# attiny_x313_blink.net
KiCad netlist of a schematic drawn in EAGLE
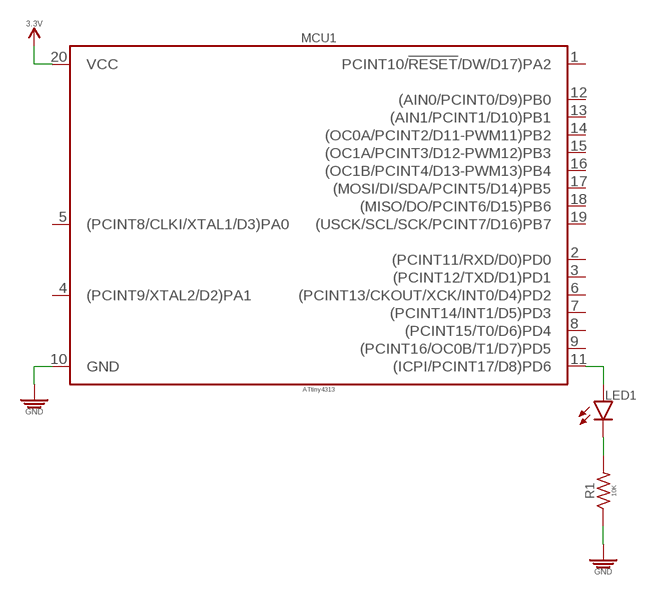
[diagram p0: schematic, sheet 1]

(export (version "E")
  (design (tool "Eeschema 10.0.6"))
  (components
    (comp (ref "LED1")
      (value "LED_PTH_T-1_3/4_5MM_NO-COLOR")
      (footprint "eagle-import:LED_PTH_T-1_3_4_5MM")
      (libsource (lib "eagle-import") (part "LED_PTH_T-1_3/4_5MM_NO-COLOR"))
    )
    (comp (ref "MCU1")
      (value "ATtiny4313")
      (footprint "eagle-import:DIP793W45P254L2573H533Q20B_DIP-20_ATTINY-X313")
      (fields (field (name "MFR") "Microchip Technology") (field (name "MPN") "ATTINY4313-PU"))
      (libsource (lib "eagle-import") (part "ATTINY-X313_DIP-20_ATTINY-4313"))
    )
    (comp (ref "R1")
      (value "10K")
      (footprint "eagle-import:RESAD660W45L340D190B")
      (fields (field (name "MFR") "Yageo") (field (name "MPN") "CFR-12JB-52-10K"))
      (libsource (lib "eagle-import") (part "10KΩ_PTH-204/7_1/6W-5%"))
    )
  )
  (nets
    (net (code "1") (name "3.3V") (class "Default")
      (node (ref "MCU1") (pin "20") (pinfunction "VCC_20") (pintype "passive"))
    )
    (net (code "2") (name "GND") (class "Default")
      (node (ref "MCU1") (pin "10") (pinfunction "GND_10") (pintype "passive"))
      (node (ref "R1") (pin "1") (pinfunction "1_1") (pintype "passive"))
    )
    (net (code "3") (name "Net-(LED1-PadK)") (class "Default")
      (node (ref "LED1") (pin "K") (pinfunction "K_K") (pintype "passive"))
      (node (ref "R1") (pin "2") (pinfunction "2_2") (pintype "passive"))
    )
    (net (code "4") (name "Net-(MCU1-(ICPI{slash}PCINT17{slash}D8)PD6)") (class "Default")
      (node (ref "LED1") (pin "A") (pinfunction "A_A") (pintype "passive"))
      (node (ref "MCU1") (pin "11") (pinfunction "(ICPI/PCINT17/D8)PD6_11") (pintype "bidirectional"))
    )
    (net (code "5") (name "unconnected-(MCU1-(AIN0{slash}PCINT0{slash}D9)PB0-Pad12)") (class "Default")
      (node (ref "MCU1") (pin "12") (pinfunction "(AIN0/PCINT0/D9)PB0_12") (pintype "bidirectional"))
    )
    (net (code "6") (name "unconnected-(MCU1-(AIN1{slash}PCINT1{slash}D10)PB1-Pad13)") (class "Default")
      (node (ref "MCU1") (pin "13") (pinfunction "(AIN1/PCINT1/D10)PB1_13") (pintype "bidirectional"))
    )
    (net (code "7") (name "unconnected-(MCU1-(MISO{slash}DO{slash}PCINT6{slash}D15)PB6-Pad18)") (class "Default")
      (node (ref "MCU1") (pin "18") (pinfunction "(MISO/DO/PCINT6/D15)PB6_18") (pintype "bidirectional"))
    )
    (net (code "8") (name "unconnected-(MCU1-(MOSI{slash}DI{slash}SDA{slash}PCINT5{slash}D14)PB5-Pad17)") (class "Default")
      (node (ref "MCU1") (pin "17") (pinfunction "(MOSI/DI/SDA/PCINT5/D14)PB5_17") (pintype "bidirectional"))
    )
    (net (code "9") (name "unconnected-(MCU1-(OC0A{slash}PCINT2{slash}D11-PWM11)PB2-Pad14)") (class "Default")
      (node (ref "MCU1") (pin "14") (pinfunction "(OC0A/PCINT2/D11-PWM11)PB2_14") (pintype "bidirectional"))
    )
    (net (code "10") (name "unconnected-(MCU1-(OC1A{slash}PCINT3{slash}D12-PWM12)PB3-Pad15)") (class "Default")
      (node (ref "MCU1") (pin "15") (pinfunction "(OC1A/PCINT3/D12-PWM12)PB3_15") (pintype "bidirectional"))
    )
    (net (code "11") (name "unconnected-(MCU1-(OC1B{slash}PCINT4{slash}D13-PWM13)PB4-Pad16)") (class "Default")
      (node (ref "MCU1") (pin "16") (pinfunction "(OC1B/PCINT4/D13-PWM13)PB4_16") (pintype "bidirectional"))
    )
    (net (code "12") (name "unconnected-(MCU1-(PCINT8{slash}CLKI{slash}XTAL1{slash}D3)PA0-Pad5)") (class "Default")
      (node (ref "MCU1") (pin "5") (pinfunction "(PCINT8/CLKI/XTAL1/D3)PA0_5") (pintype "bidirectional"))
    )
    (net (code "13") (name "unconnected-(MCU1-(PCINT9{slash}XTAL2{slash}D2)PA1-Pad4)") (class "Default")
      (node (ref "MCU1") (pin "4") (pinfunction "(PCINT9/XTAL2/D2)PA1_4") (pintype "bidirectional"))
    )
    (net (code "14") (name "unconnected-(MCU1-(PCINT11{slash}RXD{slash}D0)PD0-Pad2)") (class "Default")
      (node (ref "MCU1") (pin "2") (pinfunction "(PCINT11/RXD/D0)PD0_2") (pintype "bidirectional"))
    )
    (net (code "15") (name "unconnected-(MCU1-(PCINT12{slash}TXD{slash}D1)PD1-Pad3)") (class "Default")
      (node (ref "MCU1") (pin "3") (pinfunction "(PCINT12/TXD/D1)PD1_3") (pintype "bidirectional"))
    )
    (net (code "16") (name "unconnected-(MCU1-(PCINT13{slash}CKOUT{slash}XCK{slash}INT0{slash}D4)PD2-Pad6)") (class "Default")
      (node (ref "MCU1") (pin "6") (pinfunction "(PCINT13/CKOUT/XCK/INT0/D4)PD2_6") (pintype "bidirectional"))
    )
    (net (code "17") (name "unconnected-(MCU1-(PCINT14{slash}INT1{slash}D5)PD3-Pad7)") (class "Default")
      (node (ref "MCU1") (pin "7") (pinfunction "(PCINT14/INT1/D5)PD3_7") (pintype "bidirectional"))
    )
    (net (code "18") (name "unconnected-(MCU1-(PCINT15{slash}T0{slash}D6)PD4-Pad8)") (class "Default")
      (node (ref "MCU1") (pin "8") (pinfunction "(PCINT15/T0/D6)PD4_8") (pintype "bidirectional"))
    )
    (net (code "19") (name "unconnected-(MCU1-(PCINT16{slash}OC0B{slash}T1{slash}D7)PD5-Pad9)") (class "Default")
      (node (ref "MCU1") (pin "9") (pinfunction "(PCINT16/OC0B/T1/D7)PD5_9") (pintype "bidirectional"))
    )
    (net (code "20") (name "unconnected-(MCU1-(USCK{slash}SCL{slash}SCK{slash}PCINT7{slash}D16)PB7-Pad19)") (class "Default")
      (node (ref "MCU1") (pin "19") (pinfunction "(USCK/SCL/SCK/PCINT7/D16)PB7_19") (pintype "bidirectional"))
    )
    (net (code "21") (name "unconnected-(MCU1-PCINT10{slash}~{RESET}{slash}DW{slash}D17)PA2-Pad1)") (class "Default")
      (node (ref "MCU1") (pin "1") (pinfunction "PCINT10/~{RESET}/DW/D17)PA2_1") (pintype "bidirectional"))
    )
  )
)
